# CPU_ETH.net
KiCad netlist of a schematic drawn in Altium Designer
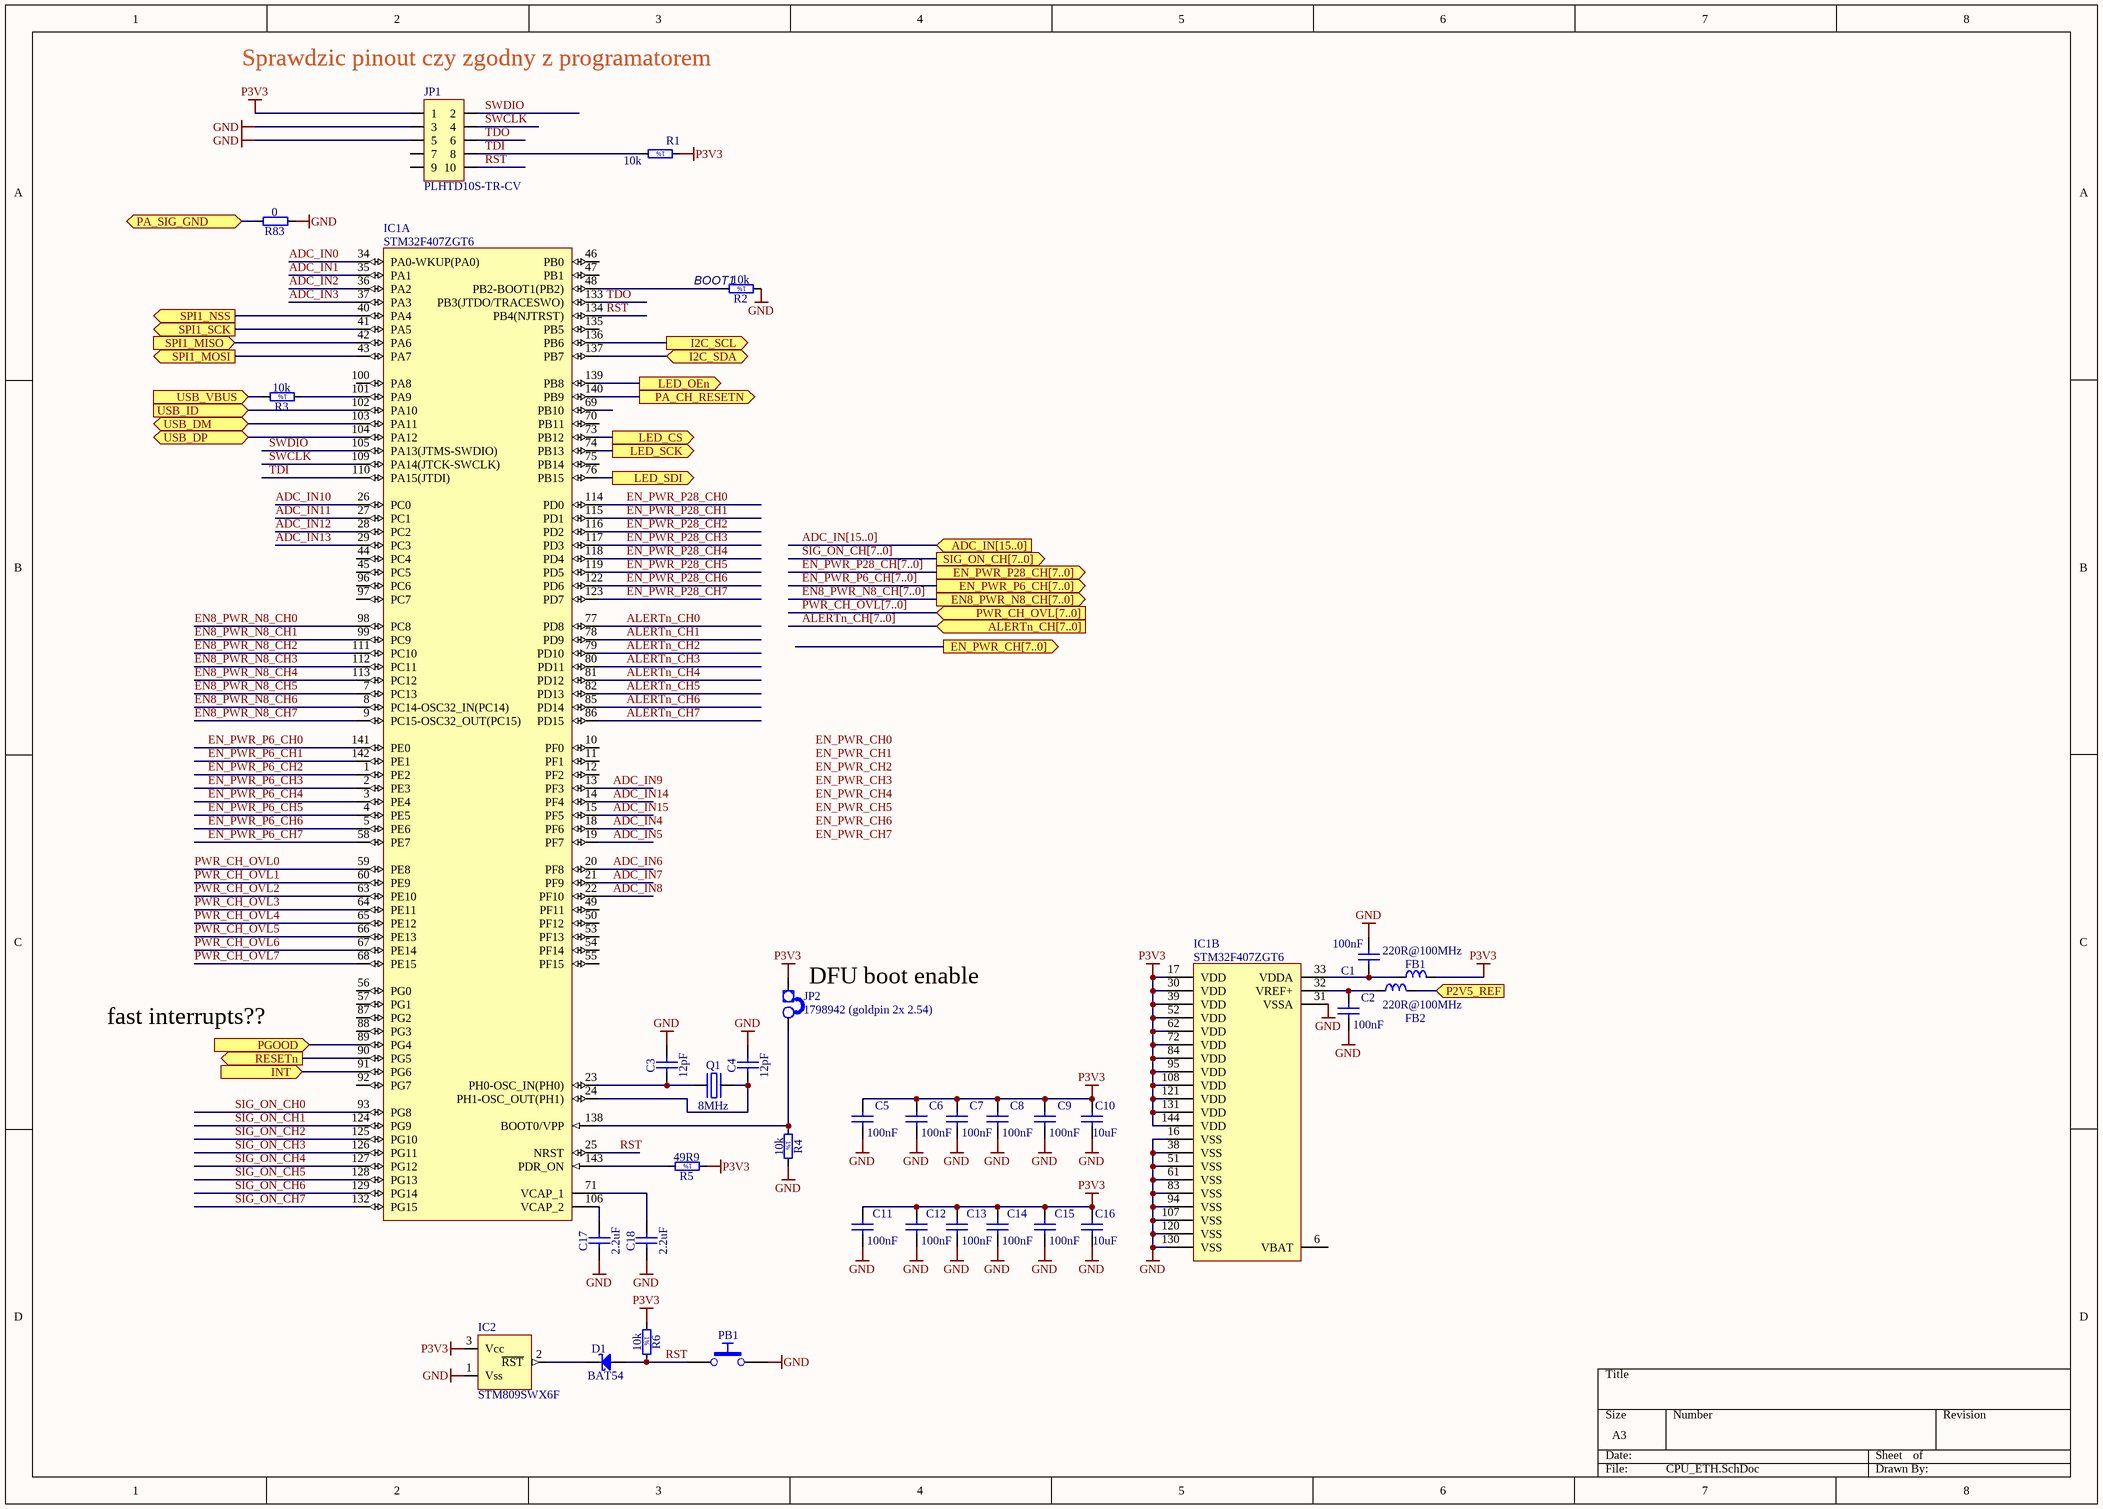
[diagram p0: CPU_ETH.SchDoc]

(export (version "E")
  (design (tool "Eeschema 10.0.6"))
  (components
    (comp (ref "C1")
      (value "100nF")
      (footprint "CAPC0603X33N")
      (description "Non-polarised capacitor")
      (fields
        (field (name "PART NUMBER") "CC0201_100NF_6.3V_10%_X5R")
        (field (name "VOLTAGE") "6.3V")
        (field (name "AUTHOR") "CERN DEM JLC")
      )
      (libsource (lib "Capacitors") (part "Capacitor - non polarized"))
    )
    (comp (ref "C2")
      (value "100nF")
      (footprint "CAPC0603X33N")
      (description "Non-polarised capacitor")
      (fields
        (field (name "PART NUMBER") "CC0201_100NF_6.3V_10%_X5R")
        (field (name "VOLTAGE") "6.3V")
        (field (name "AUTHOR") "CERN DEM JLC")
      )
      (libsource (lib "Capacitors") (part "Capacitor - non polarized"))
    )
    (comp (ref "C3")
      (value "12pF")
      (footprint "CAPC1005X55N")
      (description "Non-polarised capacitor")
      (fields
        (field (name "PART NUMBER") "CC0402_12PF_50V_5%_C0G")
        (field (name "VOLTAGE") "50V")
        (field (name "AUTHOR") "CERN DEM JLC")
      )
      (libsource (lib "Capacitors") (part "Capacitor - non polarized"))
    )
    (comp (ref "C4")
      (value "12pF")
      (footprint "CAPC1005X55N")
      (description "Non-polarised capacitor")
      (fields
        (field (name "PART NUMBER") "CC0402_12PF_50V_5%_C0G")
        (field (name "VOLTAGE") "50V")
        (field (name "AUTHOR") "CERN DEM JLC")
      )
      (libsource (lib "Capacitors") (part "Capacitor - non polarized"))
    )
    (comp (ref "C5")
      (value "100nF")
      (footprint "CAPC0603X33N")
      (description "Non-polarised capacitor")
      (fields
        (field (name "PART NUMBER") "CC0201_100NF_6.3V_10%_X5R")
        (field (name "VOLTAGE") "6.3V")
        (field (name "AUTHOR") "CERN DEM JLC")
      )
      (libsource (lib "Capacitors") (part "Capacitor - non polarized"))
    )
    (comp (ref "C6")
      (value "100nF")
      (footprint "CAPC0603X33N")
      (description "Non-polarised capacitor")
      (fields
        (field (name "PART NUMBER") "CC0201_100NF_6.3V_10%_X5R")
        (field (name "VOLTAGE") "6.3V")
        (field (name "AUTHOR") "CERN DEM JLC")
      )
      (libsource (lib "Capacitors") (part "Capacitor - non polarized"))
    )
    (comp (ref "C7")
      (value "100nF")
      (footprint "CAPC0603X33N")
      (description "Non-polarised capacitor")
      (fields
        (field (name "PART NUMBER") "CC0201_100NF_6.3V_10%_X5R")
        (field (name "VOLTAGE") "6.3V")
        (field (name "AUTHOR") "CERN DEM JLC")
      )
      (libsource (lib "Capacitors") (part "Capacitor - non polarized"))
    )
    (comp (ref "C8")
      (value "100nF")
      (footprint "CAPC0603X33N")
      (description "Non-polarised capacitor")
      (fields
        (field (name "PART NUMBER") "CC0201_100NF_6.3V_10%_X5R")
        (field (name "VOLTAGE") "6.3V")
        (field (name "AUTHOR") "CERN DEM JLC")
      )
      (libsource (lib "Capacitors") (part "Capacitor - non polarized"))
    )
    (comp (ref "C9")
      (value "100nF")
      (footprint "CAPC0603X33N")
      (description "Non-polarised capacitor")
      (fields
        (field (name "PART NUMBER") "CC0201_100NF_6.3V_10%_X5R")
        (field (name "VOLTAGE") "6.3V")
        (field (name "AUTHOR") "CERN DEM JLC")
      )
      (libsource (lib "Capacitors") (part "Capacitor - non polarized"))
    )
    (comp (ref "C10")
      (value "10uF")
      (footprint "CAPC2012X135N")
      (description "Non-polarised capacitor")
      (fields
        (field (name "PART NUMBER") "CC0805_10UF_10V_10%_X7R")
        (field (name "VOLTAGE") "10V")
        (field (name "AUTHOR") "CERN DEM JLC")
      )
      (libsource (lib "Capacitors") (part "Capacitor - non polarized"))
    )
    (comp (ref "C11")
      (value "100nF")
      (footprint "CAPC0603X33N")
      (description "Non-polarised capacitor")
      (fields
        (field (name "PART NUMBER") "CC0201_100NF_6.3V_10%_X5R")
        (field (name "VOLTAGE") "6.3V")
        (field (name "AUTHOR") "CERN DEM JLC")
      )
      (libsource (lib "Capacitors") (part "Capacitor - non polarized"))
    )
    (comp (ref "C12")
      (value "100nF")
      (footprint "CAPC0603X33N")
      (description "Non-polarised capacitor")
      (fields
        (field (name "PART NUMBER") "CC0201_100NF_6.3V_10%_X5R")
        (field (name "VOLTAGE") "6.3V")
        (field (name "AUTHOR") "CERN DEM JLC")
      )
      (libsource (lib "Capacitors") (part "Capacitor - non polarized"))
    )
    (comp (ref "C13")
      (value "100nF")
      (footprint "CAPC0603X33N")
      (description "Non-polarised capacitor")
      (fields
        (field (name "PART NUMBER") "CC0201_100NF_6.3V_10%_X5R")
        (field (name "VOLTAGE") "6.3V")
        (field (name "AUTHOR") "CERN DEM JLC")
      )
      (libsource (lib "Capacitors") (part "Capacitor - non polarized"))
    )
    (comp (ref "C14")
      (value "100nF")
      (footprint "CAPC0603X33N")
      (description "Non-polarised capacitor")
      (fields
        (field (name "PART NUMBER") "CC0201_100NF_6.3V_10%_X5R")
        (field (name "VOLTAGE") "6.3V")
        (field (name "AUTHOR") "CERN DEM JLC")
      )
      (libsource (lib "Capacitors") (part "Capacitor - non polarized"))
    )
    (comp (ref "C15")
      (value "100nF")
      (footprint "CAPC0603X33N")
      (description "Non-polarised capacitor")
      (fields
        (field (name "PART NUMBER") "CC0201_100NF_6.3V_10%_X5R")
        (field (name "VOLTAGE") "6.3V")
        (field (name "AUTHOR") "CERN DEM JLC")
      )
      (libsource (lib "Capacitors") (part "Capacitor - non polarized"))
    )
    (comp (ref "C16")
      (value "10uF")
      (footprint "CAPC2012X135N")
      (description "Non-polarised capacitor")
      (fields
        (field (name "PART NUMBER") "CC0805_10UF_10V_10%_X7R")
        (field (name "VOLTAGE") "10V")
        (field (name "AUTHOR") "CERN DEM JLC")
      )
      (libsource (lib "Capacitors") (part "Capacitor - non polarized"))
    )
    (comp (ref "C17")
      (value "2.2uF")
      (footprint "CAPC1608X90N")
      (description "Non-polarised capacitor")
      (fields
        (field (name "PART NUMBER") "CC0603_2.2UF_10V_20%_X7R")
        (field (name "VOLTAGE") "10V")
        (field (name "AUTHOR") "CERN DEM JLC")
      )
      (libsource (lib "Capacitors") (part "Capacitor - non polarized"))
    )
    (comp (ref "C18")
      (value "2.2uF")
      (footprint "CAPC1608X90N")
      (description "Non-polarised capacitor")
      (fields
        (field (name "PART NUMBER") "CC0603_2.2UF_10V_20%_X7R")
        (field (name "VOLTAGE") "10V")
        (field (name "AUTHOR") "CERN DEM JLC")
      )
      (libsource (lib "Capacitors") (part "Capacitor - non polarized"))
    )
    (comp (ref "D1")
      (value "BAT54")
      (footprint "SOT95P240X130-3N")
      (description "Diode Schottky  Anode Pin 1 Cathode Pin 3 (Pas de pin 2)")
      (fields
        (field (name "VOLTAGE") "30V")
        (field (name "POWER") "200mA")
        (field (name "AUTHOR") "CERN DEM JLC")
      )
      (libsource (lib "ICs And Semiconductors") (part "Diode Schottky A1C3"))
    )
    (comp (ref "FB1")
      (value "220R@100MHz")
      (footprint "INDC2012X105N")
      (description "Inductor")
      (fields
        (field (name "PART NUMBER") "IND0805_MURATA_BLM21PG221SN1D")
        (field (name "POWER") "2A")
        (field (name "AUTHOR") "CERN DEM JLC")
      )
      (libsource (lib "Inductors & Transformers") (part "Inductor"))
    )
    (comp (ref "FB2")
      (value "220R@100MHz")
      (footprint "INDC2012X105N")
      (description "Inductor")
      (fields
        (field (name "PART NUMBER") "IND0805_MURATA_BLM21PG221SN1D")
        (field (name "POWER") "2A")
        (field (name "AUTHOR") "CERN DEM JLC")
      )
      (libsource (lib "Inductors & Transformers") (part "Inductor"))
    )
    (comp (ref "IC1")
      (value "STM32F407ZGT6")
      (footprint "QFP50P2200X2200X160-144N")
      (fields (field (name "MANUFACTURER") "ST MICROELECTRONICS") (field (name "AUTHOR") "CERN DEM MR"))
      (libsource (lib "ICs And Semiconductors") (part "STM32F407ZGT6"))
    )
    (comp (ref "IC2")
      (value "STM809SWX6F")
      (footprint "SOT-23")
      (description "2.93V  Reset circuit")
      (libsource (lib "LIBRARY_SCH") (part "VMON_STM809"))
    )
    (comp (ref "JP1")
      (value "PLHTD10S-TR-CV")
      (footprint "PLHTD10S-TR-CV")
      (description "1.27 mm dual row goldpin (Maritex)")
      (libsource (lib "LIBRARY_SCH") (part "CON_2x5 1.27 SMT Male"))
    )
    (comp (ref "JP2")
      (value "1798942 (goldpin 2x 2.54)")
      (footprint "jump")
      (description "Jumper")
      (libsource (lib "LIBRARY_SCH") (part "JUMPER"))
    )
    (comp (ref "PB1")
      (value "Push Button")
      (footprint "PB_TYCO_FSMSM")
      (description "Push-Button Switch SPDT")
      (fields
        (field (name "PART NUMBER") "PB_TYCO_FSMSM")
        (field (name "MANUFACTURER") "TYCO ELECTRONICS")
        (field (name "AUTHOR") "CERN DEM JLC")
      )
      (libsource (lib "Eletro-mechanical") (part "PB SPST 1NO-2NO"))
    )
    (comp (ref "Q1")
      (value "8MHz")
      (footprint "XTAL_TXC_7A")
      (description "Quartz Crystal")
      (fields
        (field (name "PART NUMBER") "XTAL_8MHZ_TXC_7A-8.000MAAE-T")
        (field (name "MANUFACTURER") "TXC CORPORATION")
        (field (name "AUTHOR") "CERN DEM JLC")
      )
      (libsource (lib "ICs And Semiconductors") (part "Quartz Crystal"))
    )
    (comp (ref "R1")
      (value "10k")
      (footprint "RESC1005X40N")
      (description "Resistor - 1%")
      (fields
        (field (name "PART NUMBER") "R0402_10K_1%_0.0625W_100PPM")
        (field (name "POWER") "0.0625W")
        (field (name "AUTHOR") "CERN DEM JLC")
      )
      (libsource (lib "Resistors") (part "Resistor - 1%"))
    )
    (comp (ref "R2")
      (value "10k")
      (footprint "RESC1005X40N")
      (description "Resistor - 1%")
      (fields
        (field (name "PART NUMBER") "R0402_10K_1%_0.0625W_100PPM")
        (field (name "POWER") "0.0625W")
        (field (name "AUTHOR") "CERN DEM JLC")
      )
      (libsource (lib "Resistors") (part "Resistor - 1%"))
    )
    (comp (ref "R3")
      (value "10k")
      (footprint "RESC1005X40N")
      (description "Resistor - 1%")
      (fields
        (field (name "PART NUMBER") "R0402_10K_1%_0.0625W_100PPM")
        (field (name "POWER") "0.0625W")
        (field (name "AUTHOR") "CERN DEM JLC")
      )
      (libsource (lib "Resistors") (part "Resistor - 1%"))
    )
    (comp (ref "R4")
      (value "10k")
      (footprint "RESC1005X40N")
      (description "Resistor - 1%")
      (fields
        (field (name "PART NUMBER") "R0402_10K_1%_0.0625W_100PPM")
        (field (name "POWER") "0.0625W")
        (field (name "AUTHOR") "CERN DEM JLC")
      )
      (libsource (lib "Resistors") (part "Resistor - 1%"))
    )
    (comp (ref "R5")
      (value "49R9")
      (footprint "RESC1005X40N")
      (description "Resistor - 1%")
      (fields
        (field (name "PART NUMBER") "R0402_49R9_1%_0.0625W_100PPM")
        (field (name "POWER") "0.0625W")
        (field (name "AUTHOR") "CERN DEM JLC")
      )
      (libsource (lib "Resistors") (part "Resistor - 1%"))
    )
    (comp (ref "R6")
      (value "10k")
      (footprint "RESC1005X40N")
      (description "Resistor - 1%")
      (fields
        (field (name "PART NUMBER") "R0402_10K_1%_0.0625W_100PPM")
        (field (name "POWER") "0.0625W")
        (field (name "AUTHOR") "CERN DEM JLC")
      )
      (libsource (lib "Resistors") (part "Resistor - 1%"))
    )
    (comp (ref "R83")
      (value "0")
      (footprint "RESC1005X40N")
      (description "Resistor")
      (fields
        (field (name "PART NUMBER") "R0402_0R_JUMPER")
        (field (name "MANUFACTURER") "GENERIC")
        (field (name "AUTHOR") "CERN DEM JLC")
      )
      (libsource (lib "Resistors") (part "Resistor"))
    )
  )
  (nets
    (net (code "1") (name "/ADC_IN0") (class "Default")
      (node (ref "IC1") (pin "34") (pinfunction "PA0-WKUP(PA0)_34") (pintype "bidirectional"))
    )
    (net (code "2") (name "/ADC_IN1") (class "Default")
      (node (ref "IC1") (pin "35") (pinfunction "PA1_35") (pintype "bidirectional"))
    )
    (net (code "3") (name "/ADC_IN2") (class "Default")
      (node (ref "IC1") (pin "36") (pinfunction "PA2_36") (pintype "bidirectional"))
    )
    (net (code "4") (name "/ADC_IN3") (class "Default")
      (node (ref "IC1") (pin "37") (pinfunction "PA3_37") (pintype "bidirectional"))
    )
    (net (code "5") (name "/ADC_IN4") (class "Default")
      (node (ref "IC1") (pin "18") (pinfunction "PF6_18") (pintype "bidirectional"))
    )
    (net (code "6") (name "/ADC_IN5") (class "Default")
      (node (ref "IC1") (pin "19") (pinfunction "PF7_19") (pintype "bidirectional"))
    )
    (net (code "7") (name "/ADC_IN6") (class "Default")
      (node (ref "IC1") (pin "20") (pinfunction "PF8_20") (pintype "bidirectional"))
    )
    (net (code "8") (name "/ADC_IN7") (class "Default")
      (node (ref "IC1") (pin "21") (pinfunction "PF9_21") (pintype "bidirectional"))
    )
    (net (code "9") (name "/ADC_IN8") (class "Default")
      (node (ref "IC1") (pin "22") (pinfunction "PF10_22") (pintype "bidirectional"))
    )
    (net (code "10") (name "/ADC_IN9") (class "Default")
      (node (ref "IC1") (pin "13") (pinfunction "PF3_13") (pintype "bidirectional"))
    )
    (net (code "11") (name "/ADC_IN10") (class "Default")
      (node (ref "IC1") (pin "26") (pinfunction "PC0_26") (pintype "bidirectional"))
    )
    (net (code "12") (name "/ADC_IN11") (class "Default")
      (node (ref "IC1") (pin "27") (pinfunction "PC1_27") (pintype "bidirectional"))
    )
    (net (code "13") (name "/ADC_IN12") (class "Default")
      (node (ref "IC1") (pin "28") (pinfunction "PC2_28") (pintype "bidirectional"))
    )
    (net (code "14") (name "/ADC_IN13") (class "Default")
      (node (ref "IC1") (pin "29") (pinfunction "PC3_29") (pintype "bidirectional"))
    )
    (net (code "15") (name "/ADC_IN14") (class "Default")
      (node (ref "IC1") (pin "14") (pinfunction "PF4_14") (pintype "bidirectional"))
    )
    (net (code "16") (name "/ADC_IN15") (class "Default")
      (node (ref "IC1") (pin "15") (pinfunction "PF5_15") (pintype "bidirectional"))
    )
    (net (code "18") (name "/ALERTn_CH0") (class "Default")
      (node (ref "IC1") (pin "77") (pinfunction "PD8_77") (pintype "bidirectional"))
    )
    (net (code "19") (name "/ALERTn_CH1") (class "Default")
      (node (ref "IC1") (pin "78") (pinfunction "PD9_78") (pintype "bidirectional"))
    )
    (net (code "20") (name "/ALERTn_CH2") (class "Default")
      (node (ref "IC1") (pin "79") (pinfunction "PD10_79") (pintype "bidirectional"))
    )
    (net (code "21") (name "/ALERTn_CH3") (class "Default")
      (node (ref "IC1") (pin "80") (pinfunction "PD11_80") (pintype "bidirectional"))
    )
    (net (code "22") (name "/ALERTn_CH4") (class "Default")
      (node (ref "IC1") (pin "81") (pinfunction "PD12_81") (pintype "bidirectional"))
    )
    (net (code "23") (name "/ALERTn_CH5") (class "Default")
      (node (ref "IC1") (pin "82") (pinfunction "PD13_82") (pintype "bidirectional"))
    )
    (net (code "24") (name "/ALERTn_CH6") (class "Default")
      (node (ref "IC1") (pin "85") (pinfunction "PD14_85") (pintype "bidirectional"))
    )
    (net (code "25") (name "/ALERTn_CH7") (class "Default")
      (node (ref "IC1") (pin "86") (pinfunction "PD15_86") (pintype "bidirectional"))
    )
    (net (code "27") (name "/EN8_PWR_N8_CH0") (class "Default")
      (node (ref "IC1") (pin "98") (pinfunction "PC8_98") (pintype "bidirectional"))
    )
    (net (code "28") (name "/EN8_PWR_N8_CH1") (class "Default")
      (node (ref "IC1") (pin "99") (pinfunction "PC9_99") (pintype "bidirectional"))
    )
    (net (code "29") (name "/EN8_PWR_N8_CH2") (class "Default")
      (node (ref "IC1") (pin "111") (pinfunction "PC10_111") (pintype "bidirectional"))
    )
    (net (code "30") (name "/EN8_PWR_N8_CH3") (class "Default")
      (node (ref "IC1") (pin "112") (pinfunction "PC11_112") (pintype "bidirectional"))
    )
    (net (code "31") (name "/EN8_PWR_N8_CH4") (class "Default")
      (node (ref "IC1") (pin "113") (pinfunction "PC12_113") (pintype "bidirectional"))
    )
    (net (code "32") (name "/EN8_PWR_N8_CH5") (class "Default")
      (node (ref "IC1") (pin "7") (pinfunction "PC13_7") (pintype "bidirectional"))
    )
    (net (code "33") (name "/EN8_PWR_N8_CH6") (class "Default")
      (node (ref "IC1") (pin "8") (pinfunction "PC14-OSC32_IN(PC14)_8") (pintype "bidirectional"))
    )
    (net (code "34") (name "/EN8_PWR_N8_CH7") (class "Default")
      (node (ref "IC1") (pin "9") (pinfunction "PC15-OSC32_OUT(PC15)_9") (pintype "bidirectional"))
    )
    (net (code "45") (name "/EN_PWR_P6_CH0") (class "Default")
      (node (ref "IC1") (pin "141") (pinfunction "PE0_141") (pintype "bidirectional"))
    )
    (net (code "46") (name "/EN_PWR_P6_CH1") (class "Default")
      (node (ref "IC1") (pin "142") (pinfunction "PE1_142") (pintype "bidirectional"))
    )
    (net (code "47") (name "/EN_PWR_P6_CH2") (class "Default")
      (node (ref "IC1") (pin "1") (pinfunction "PE2_1") (pintype "bidirectional"))
    )
    (net (code "48") (name "/EN_PWR_P6_CH3") (class "Default")
      (node (ref "IC1") (pin "2") (pinfunction "PE3_2") (pintype "bidirectional"))
    )
    (net (code "49") (name "/EN_PWR_P6_CH4") (class "Default")
      (node (ref "IC1") (pin "3") (pinfunction "PE4_3") (pintype "bidirectional"))
    )
    (net (code "50") (name "/EN_PWR_P6_CH5") (class "Default")
      (node (ref "IC1") (pin "4") (pinfunction "PE5_4") (pintype "bidirectional"))
    )
    (net (code "51") (name "/EN_PWR_P6_CH6") (class "Default")
      (node (ref "IC1") (pin "5") (pinfunction "PE6_5") (pintype "bidirectional"))
    )
    (net (code "52") (name "/EN_PWR_P6_CH7") (class "Default")
      (node (ref "IC1") (pin "58") (pinfunction "PE7_58") (pintype "bidirectional"))
    )
    (net (code "54") (name "/EN_PWR_P28_CH0") (class "Default")
      (node (ref "IC1") (pin "114") (pinfunction "PD0_114") (pintype "bidirectional"))
    )
    (net (code "55") (name "/EN_PWR_P28_CH1") (class "Default")
      (node (ref "IC1") (pin "115") (pinfunction "PD1_115") (pintype "bidirectional"))
    )
    (net (code "56") (name "/EN_PWR_P28_CH2") (class "Default")
      (node (ref "IC1") (pin "116") (pinfunction "PD2_116") (pintype "bidirectional"))
    )
    (net (code "57") (name "/EN_PWR_P28_CH3") (class "Default")
      (node (ref "IC1") (pin "117") (pinfunction "PD3_117") (pintype "bidirectional"))
    )
    (net (code "58") (name "/EN_PWR_P28_CH4") (class "Default")
      (node (ref "IC1") (pin "118") (pinfunction "PD4_118") (pintype "bidirectional"))
    )
    (net (code "59") (name "/EN_PWR_P28_CH5") (class "Default")
      (node (ref "IC1") (pin "119") (pinfunction "PD5_119") (pintype "bidirectional"))
    )
    (net (code "60") (name "/EN_PWR_P28_CH6") (class "Default")
      (node (ref "IC1") (pin "122") (pinfunction "PD6_122") (pintype "bidirectional"))
    )
    (net (code "61") (name "/EN_PWR_P28_CH7") (class "Default")
      (node (ref "IC1") (pin "123") (pinfunction "PD7_123") (pintype "bidirectional"))
    )
    (net (code "63") (name "/I2C_SCL") (class "Default")
      (node (ref "IC1") (pin "136") (pinfunction "PB6_136") (pintype "bidirectional"))
    )
    (net (code "64") (name "/I2C_SDA") (class "Default")
      (node (ref "IC1") (pin "137") (pinfunction "PB7_137") (pintype "bidirectional"))
    )
    (net (code "65") (name "/INT") (class "Default")
      (node (ref "IC1") (pin "91") (pinfunction "PG6_91") (pintype "bidirectional"))
    )
    (net (code "66") (name "/LED_CS") (class "Default")
      (node (ref "IC1") (pin "73") (pinfunction "PB12_73") (pintype "bidirectional"))
    )
    (net (code "67") (name "/LED_OEn") (class "Default")
      (node (ref "IC1") (pin "139") (pinfunction "PB8_139") (pintype "bidirectional"))
    )
    (net (code "68") (name "/LED_SCK") (class "Default")
      (node (ref "IC1") (pin "74") (pinfunction "PB13_74") (pintype "bidirectional"))
    )
    (net (code "69") (name "/LED_SDI") (class "Default")
      (node (ref "IC1") (pin "76") (pinfunction "PB15_76") (pintype "bidirectional"))
    )
    (net (code "70") (name "/P2V5_REF") (class "Default")
      (node (ref "FB2") (pin "2") (pinfunction "2_2") (pintype "passive"))
    )
    (net (code "71") (name "/PA_CH_RESETN") (class "Default")
      (node (ref "IC1") (pin "140") (pinfunction "PB9_140") (pintype "bidirectional"))
    )
    (net (code "72") (name "/PA_SIG_GND") (class "Default")
      (node (ref "R83") (pin "2") (pinfunction "2_2") (pintype "passive"))
    )
    (net (code "73") (name "/PGOOD") (class "Default")
      (node (ref "IC1") (pin "89") (pinfunction "PG4_89") (pintype "bidirectional"))
    )
    (net (code "74") (name "/PWR_CH_OVL0") (class "Default")
      (node (ref "IC1") (pin "59") (pinfunction "PE8_59") (pintype "bidirectional"))
    )
    (net (code "75") (name "/PWR_CH_OVL1") (class "Default")
      (node (ref "IC1") (pin "60") (pinfunction "PE9_60") (pintype "bidirectional"))
    )
    (net (code "76") (name "/PWR_CH_OVL2") (class "Default")
      (node (ref "IC1") (pin "63") (pinfunction "PE10_63") (pintype "bidirectional"))
    )
    (net (code "77") (name "/PWR_CH_OVL3") (class "Default")
      (node (ref "IC1") (pin "64") (pinfunction "PE11_64") (pintype "bidirectional"))
    )
    (net (code "78") (name "/PWR_CH_OVL4") (class "Default")
      (node (ref "IC1") (pin "65") (pinfunction "PE12_65") (pintype "bidirectional"))
    )
    (net (code "79") (name "/PWR_CH_OVL5") (class "Default")
      (node (ref "IC1") (pin "66") (pinfunction "PE13_66") (pintype "bidirectional"))
    )
    (net (code "80") (name "/PWR_CH_OVL6") (class "Default")
      (node (ref "IC1") (pin "67") (pinfunction "PE14_67") (pintype "bidirectional"))
    )
    (net (code "81") (name "/PWR_CH_OVL7") (class "Default")
      (node (ref "IC1") (pin "68") (pinfunction "PE15_68") (pintype "bidirectional"))
    )
    (net (code "83") (name "/RESETn") (class "Default")
      (node (ref "IC1") (pin "90") (pinfunction "PG5_90") (pintype "bidirectional"))
    )
    (net (code "84") (name "/RST") (class "Default")
      (node (ref "D1") (pin "1") (pinfunction "A_1") (pintype "passive"))
      (node (ref "IC1") (pin "134") (pinfunction "PB4(NJTRST)_134") (pintype "bidirectional"))
      (node (ref "IC1") (pin "25") (pinfunction "NRST_25") (pintype "bidirectional"))
      (node (ref "JP1") (pin "10") (pinfunction "10_10") (pintype "passive"))
      (node (ref "PB1") (pin "1") (pinfunction "1_1") (pintype "passive"))
      (node (ref "R6") (pin "2") (pinfunction "2_2") (pintype "passive"))
    )
    (net (code "85") (name "/SIG_ON_CH0") (class "Default")
      (node (ref "IC1") (pin "93") (pinfunction "PG8_93") (pintype "bidirectional"))
    )
    (net (code "86") (name "/SIG_ON_CH1") (class "Default")
      (node (ref "IC1") (pin "124") (pinfunction "PG9_124") (pintype "bidirectional"))
    )
    (net (code "87") (name "/SIG_ON_CH2") (class "Default")
      (node (ref "IC1") (pin "125") (pinfunction "PG10_125") (pintype "bidirectional"))
    )
    (net (code "88") (name "/SIG_ON_CH3") (class "Default")
      (node (ref "IC1") (pin "126") (pinfunction "PG11_126") (pintype "bidirectional"))
    )
    (net (code "89") (name "/SIG_ON_CH4") (class "Default")
      (node (ref "IC1") (pin "127") (pinfunction "PG12_127") (pintype "bidirectional"))
    )
    (net (code "90") (name "/SIG_ON_CH5") (class "Default")
      (node (ref "IC1") (pin "128") (pinfunction "PG13_128") (pintype "bidirectional"))
    )
    (net (code "91") (name "/SIG_ON_CH6") (class "Default")
      (node (ref "IC1") (pin "129") (pinfunction "PG14_129") (pintype "bidirectional"))
    )
    (net (code "92") (name "/SIG_ON_CH7") (class "Default")
      (node (ref "IC1") (pin "132") (pinfunction "PG15_132") (pintype "bidirectional"))
    )
    (net (code "94") (name "/SPI1_MISO") (class "Default")
      (node (ref "IC1") (pin "42") (pinfunction "PA6_42") (pintype "bidirectional"))
    )
    (net (code "95") (name "/SPI1_MOSI") (class "Default")
      (node (ref "IC1") (pin "43") (pinfunction "PA7_43") (pintype "bidirectional"))
    )
    (net (code "96") (name "/SPI1_NSS") (class "Default")
      (node (ref "IC1") (pin "40") (pinfunction "PA4_40") (pintype "bidirectional"))
    )
    (net (code "97") (name "/SPI1_SCK") (class "Default")
      (node (ref "IC1") (pin "41") (pinfunction "PA5_41") (pintype "bidirectional"))
    )
    (net (code "98") (name "/SWCLK") (class "Default")
      (node (ref "IC1") (pin "109") (pinfunction "PA14(JTCK-SWCLK)_109") (pintype "bidirectional"))
      (node (ref "JP1") (pin "4") (pinfunction "4_4") (pintype "passive"))
    )
    (net (code "99") (name "/SWDIO") (class "Default")
      (node (ref "IC1") (pin "105") (pinfunction "PA13(JTMS-SWDIO)_105") (pintype "bidirectional"))
      (node (ref "JP1") (pin "2") (pinfunction "2_2") (pintype "passive"))
    )
    (net (code "100") (name "/TDI") (class "Default")
      (node (ref "IC1") (pin "110") (pinfunction "PA15(JTDI)_110") (pintype "bidirectional"))
      (node (ref "JP1") (pin "8") (pinfunction "8_8") (pintype "passive"))
      (node (ref "R1") (pin "2") (pinfunction "2_2") (pintype "passive"))
    )
    (net (code "101") (name "/TDO") (class "Default")
      (node (ref "IC1") (pin "133") (pinfunction "PB3(JTDO/TRACESWO)_133") (pintype "bidirectional"))
      (node (ref "JP1") (pin "6") (pinfunction "6_6") (pintype "passive"))
    )
    (net (code "102") (name "/USB_DM") (class "Default")
      (node (ref "IC1") (pin "103") (pinfunction "PA11_103") (pintype "bidirectional"))
    )
    (net (code "103") (name "/USB_DP") (class "Default")
      (node (ref "IC1") (pin "104") (pinfunction "PA12_104") (pintype "bidirectional"))
    )
    (net (code "104") (name "/USB_ID") (class "Default")
      (node (ref "IC1") (pin "102") (pinfunction "PA10_102") (pintype "bidirectional"))
    )
    (net (code "105") (name "/USB_VBUS") (class "Default")
      (node (ref "R3") (pin "2") (pinfunction "2_2") (pintype "passive"))
    )
    (net (code "106") (name "GND") (class "Default")
      (node (ref "C1") (pin "2") (pinfunction "2_2") (pintype "passive"))
      (node (ref "C10") (pin "2") (pinfunction "2_2") (pintype "passive"))
      (node (ref "C11") (pin "2") (pinfunction "2_2") (pintype "passive"))
      (node (ref "C12") (pin "2") (pinfunction "2_2") (pintype "passive"))
      (node (ref "C13") (pin "2") (pinfunction "2_2") (pintype "passive"))
      (node (ref "C14") (pin "2") (pinfunction "2_2") (pintype "passive"))
      (node (ref "C15") (pin "2") (pinfunction "2_2") (pintype "passive"))
      (node (ref "C16") (pin "2") (pinfunction "2_2") (pintype "passive"))
      (node (ref "C17") (pin "1") (pinfunction "1_1") (pintype "passive"))
      (node (ref "C18") (pin "1") (pinfunction "1_1") (pintype "passive"))
      (node (ref "C2") (pin "2") (pinfunction "2_2") (pintype "passive"))
      (node (ref "C3") (pin "2") (pinfunction "2_2") (pintype "passive"))
      (node (ref "C4") (pin "2") (pinfunction "2_2") (pintype "passive"))
      (node (ref "C5") (pin "2") (pinfunction "2_2") (pintype "passive"))
      (node (ref "C6") (pin "2") (pinfunction "2_2") (pintype "passive"))
      (node (ref "C7") (pin "2") (pinfunction "2_2") (pintype "passive"))
      (node (ref "C8") (pin "2") (pinfunction "2_2") (pintype "passive"))
      (node (ref "C9") (pin "2") (pinfunction "2_2") (pintype "passive"))
      (node (ref "IC1") (pin "107") (pinfunction "VSS_107") (pintype "power_in"))
      (node (ref "IC1") (pin "120") (pinfunction "VSS_120") (pintype "power_in"))
      (node (ref "IC1") (pin "130") (pinfunction "VSS_130") (pintype "power_in"))
      (node (ref "IC1") (pin "16") (pinfunction "VSS_16") (pintype "power_in"))
      (node (ref "IC1") (pin "31") (pinfunction "VSSA_31") (pintype "power_in"))
      (node (ref "IC1") (pin "38") (pinfunction "VSS_38") (pintype "power_in"))
      (node (ref "IC1") (pin "51") (pinfunction "VSS_51") (pintype "power_in"))
      (node (ref "IC1") (pin "61") (pinfunction "VSS_61") (pintype "power_in"))
      (node (ref "IC1") (pin "83") (pinfunction "VSS_83") (pintype "power_in"))
      (node (ref "IC1") (pin "94") (pinfunction "VSS_94") (pintype "power_in"))
      (node (ref "IC2") (pin "1") (pinfunction "Vss_1") (pintype "power_in"))
      (node (ref "JP1") (pin "3") (pinfunction "3_3") (pintype "passive"))
      (node (ref "JP1") (pin "5") (pinfunction "5_5") (pintype "passive"))
      (node (ref "PB1") (pin "2") (pinfunction "2_2") (pintype "passive"))
      (node (ref "R2") (pin "1") (pinfunction "1_1") (pintype "passive"))
      (node (ref "R4") (pin "2") (pinfunction "2_2") (pintype "passive"))
      (node (ref "R83") (pin "1") (pinfunction "1_1") (pintype "passive"))
    )
    (net (code "107") (name "Net-(D1-C)") (class "Default")
      (node (ref "D1") (pin "3") (pinfunction "C_3") (pintype "passive"))
      (node (ref "IC2") (pin "2") (pinfunction "~{RST}_2") (pintype "output"))
    )
    (net (code "108") (name "Net-(IC1A-BOOT0{slash}VPP)") (class "Default")
      (node (ref "IC1") (pin "138") (pinfunction "BOOT0/VPP_138") (pintype "input"))
      (node (ref "JP2") (pin "2") (pinfunction "E2_2") (pintype "passive"))
      (node (ref "R4") (pin "1") (pinfunction "1_1") (pintype "passive"))
    )
    (net (code "109") (name "Net-(IC1A-PA9)") (class "Default")
      (node (ref "IC1") (pin "101") (pinfunction "PA9_101") (pintype "bidirectional"))
      (node (ref "R3") (pin "1") (pinfunction "1_1") (pintype "passive"))
    )
    (net (code "110") (name "Net-(IC1A-PB2-BOOT1(PB2))") (class "Default")
      (node (ref "IC1") (pin "48") (pinfunction "PB2-BOOT1(PB2)_48") (pintype "bidirectional"))
      (node (ref "R2") (pin "2") (pinfunction "2_2") (pintype "passive"))
    )
    (net (code "111") (name "Net-(IC1A-PDR_ON)") (class "Default")
      (node (ref "IC1") (pin "143") (pinfunction "PDR_ON_143") (pintype "input"))
      (node (ref "R5") (pin "2") (pinfunction "2_2") (pintype "passive"))
    )
    (net (code "112") (name "Net-(IC1A-PH0-OSC_IN(PH0))") (class "Default")
      (node (ref "C3") (pin "1") (pinfunction "1_1") (pintype "passive"))
      (node (ref "IC1") (pin "23") (pinfunction "PH0-OSC_IN(PH0)_23") (pintype "bidirectional"))
      (node (ref "Q1") (pin "1") (pinfunction "OSC1_1") (pintype "passive"))
    )
    (net (code "113") (name "Net-(IC1A-PH1-OSC_OUT(PH1))") (class "Default")
      (node (ref "C4") (pin "1") (pinfunction "1_1") (pintype "passive"))
      (node (ref "IC1") (pin "24") (pinfunction "PH1-OSC_OUT(PH1)_24") (pintype "bidirectional"))
      (node (ref "Q1") (pin "2") (pinfunction "OSC2_2") (pintype "passive"))
    )
    (net (code "114") (name "Net-(IC1A-VCAP_1)") (class "Default")
      (node (ref "C18") (pin "2") (pinfunction "2_2") (pintype "passive"))
      (node (ref "IC1") (pin "71") (pinfunction "VCAP_1_71") (pintype "power_in"))
    )
    (net (code "115") (name "Net-(IC1A-VCAP_2)") (class "Default")
      (node (ref "C17") (pin "2") (pinfunction "2_2") (pintype "passive"))
      (node (ref "IC1") (pin "106") (pinfunction "VCAP_2_106") (pintype "power_in"))
    )
    (net (code "116") (name "Net-(IC1B-VDDA)") (class "Default")
      (node (ref "C1") (pin "1") (pinfunction "1_1") (pintype "passive"))
      (node (ref "FB1") (pin "1") (pinfunction "1_1") (pintype "passive"))
      (node (ref "IC1") (pin "33") (pinfunction "VDDA_33") (pintype "power_in"))
    )
    (net (code "117") (name "Net-(IC1B-VREF+)") (class "Default")
      (node (ref "C2") (pin "1") (pinfunction "1_1") (pintype "passive"))
      (node (ref "FB2") (pin "1") (pinfunction "1_1") (pintype "passive"))
      (node (ref "IC1") (pin "32") (pinfunction "VREF+_32") (pintype "power_in"))
    )
    (net (code "118") (name "P3V3") (class "Default")
      (node (ref "C10") (pin "1") (pinfunction "1_1") (pintype "passive"))
      (node (ref "C11") (pin "1") (pinfunction "1_1") (pintype "passive"))
      (node (ref "C12") (pin "1") (pinfunction "1_1") (pintype "passive"))
      (node (ref "C13") (pin "1") (pinfunction "1_1") (pintype "passive"))
      (node (ref "C14") (pin "1") (pinfunction "1_1") (pintype "passive"))
      (node (ref "C15") (pin "1") (pinfunction "1_1") (pintype "passive"))
      (node (ref "C16") (pin "1") (pinfunction "1_1") (pintype "passive"))
      (node (ref "C5") (pin "1") (pinfunction "1_1") (pintype "passive"))
      (node (ref "C6") (pin "1") (pinfunction "1_1") (pintype "passive"))
      (node (ref "C7") (pin "1") (pinfunction "1_1") (pintype "passive"))
      (node (ref "C8") (pin "1") (pinfunction "1_1") (pintype "passive"))
      (node (ref "C9") (pin "1") (pinfunction "1_1") (pintype "passive"))
      (node (ref "FB1") (pin "2") (pinfunction "2_2") (pintype "passive"))
      (node (ref "IC1") (pin "108") (pinfunction "VDD_108") (pintype "power_in"))
      (node (ref "IC1") (pin "121") (pinfunction "VDD_121") (pintype "power_in"))
      (node (ref "IC1") (pin "131") (pinfunction "VDD_131") (pintype "power_in"))
      (node (ref "IC1") (pin "144") (pinfunction "VDD_144") (pintype "power_in"))
      (node (ref "IC1") (pin "17") (pinfunction "VDD_17") (pintype "power_in"))
      (node (ref "IC1") (pin "30") (pinfunction "VDD_30") (pintype "power_in"))
      (node (ref "IC1") (pin "39") (pinfunction "VDD_39") (pintype "power_in"))
      (node (ref "IC1") (pin "52") (pinfunction "VDD_52") (pintype "power_in"))
      (node (ref "IC1") (pin "62") (pinfunction "VDD_62") (pintype "power_in"))
      (node (ref "IC1") (pin "72") (pinfunction "VDD_72") (pintype "power_in"))
      (node (ref "IC1") (pin "84") (pinfunction "VDD_84") (pintype "power_in"))
      (node (ref "IC1") (pin "95") (pinfunction "VDD_95") (pintype "power_in"))
      (node (ref "IC2") (pin "3") (pinfunction "Vcc_3") (pintype "power_in"))
      (node (ref "JP1") (pin "1") (pinfunction "1_1") (pintype "passive"))
      (node (ref "JP2") (pin "1") (pinfunction "E1_1") (pintype "passive"))
      (node (ref "R1") (pin "1") (pinfunction "1_1") (pintype "passive"))
      (node (ref "R5") (pin "1") (pinfunction "1_1") (pintype "passive"))
      (node (ref "R6") (pin "1") (pinfunction "1_1") (pintype "passive"))
    )
    (net (code "119") (name "unconnected-(IC1A-PA8-Pad100)") (class "Default")
      (node (ref "IC1") (pin "100") (pinfunction "PA8_100") (pintype "bidirectional"))
    )
    (net (code "120") (name "unconnected-(IC1A-PB0-Pad46)") (class "Default")
      (node (ref "IC1") (pin "46") (pinfunction "PB0_46") (pintype "bidirectional"))
    )
    (net (code "121") (name "unconnected-(IC1A-PB1-Pad47)") (class "Default")
      (node (ref "IC1") (pin "47") (pinfunction "PB1_47") (pintype "bidirectional"))
    )
    (net (code "122") (name "unconnected-(IC1A-PB5-Pad135)") (class "Default")
      (node (ref "IC1") (pin "135") (pinfunction "PB5_135") (pintype "bidirectional"))
    )
    (net (code "123") (name "unconnected-(IC1A-PB10-Pad69)") (class "Default")
      (node (ref "IC1") (pin "69") (pinfunction "PB10_69") (pintype "bidirectional"))
    )
    (net (code "124") (name "unconnected-(IC1A-PB11-Pad70)") (class "Default")
      (node (ref "IC1") (pin "70") (pinfunction "PB11_70") (pintype "bidirectional"))
    )
    (net (code "125") (name "unconnected-(IC1A-PB14-Pad75)") (class "Default")
      (node (ref "IC1") (pin "75") (pinfunction "PB14_75") (pintype "bidirectional"))
    )
    (net (code "126") (name "unconnected-(IC1A-PC4-Pad44)") (class "Default")
      (node (ref "IC1") (pin "44") (pinfunction "PC4_44") (pintype "bidirectional"))
    )
    (net (code "127") (name "unconnected-(IC1A-PC5-Pad45)") (class "Default")
      (node (ref "IC1") (pin "45") (pinfunction "PC5_45") (pintype "bidirectional"))
    )
    (net (code "128") (name "unconnected-(IC1A-PC6-Pad96)") (class "Default")
      (node (ref "IC1") (pin "96") (pinfunction "PC6_96") (pintype "bidirectional"))
    )
    (net (code "129") (name "unconnected-(IC1A-PC7-Pad97)") (class "Default")
      (node (ref "IC1") (pin "97") (pinfunction "PC7_97") (pintype "bidirectional"))
    )
    (net (code "130") (name "unconnected-(IC1A-PF0-Pad10)") (class "Default")
      (node (ref "IC1") (pin "10") (pinfunction "PF0_10") (pintype "bidirectional"))
    )
    (net (code "131") (name "unconnected-(IC1A-PF1-Pad11)") (class "Default")
      (node (ref "IC1") (pin "11") (pinfunction "PF1_11") (pintype "bidirectional"))
    )
    (net (code "132") (name "unconnected-(IC1A-PF2-Pad12)") (class "Default")
      (node (ref "IC1") (pin "12") (pinfunction "PF2_12") (pintype "bidirectional"))
    )
    (net (code "133") (name "unconnected-(IC1A-PF11-Pad49)") (class "Default")
      (node (ref "IC1") (pin "49") (pinfunction "PF11_49") (pintype "bidirectional"))
    )
    (net (code "134") (name "unconnected-(IC1A-PF12-Pad50)") (class "Default")
      (node (ref "IC1") (pin "50") (pinfunction "PF12_50") (pintype "bidirectional"))
    )
    (net (code "135") (name "unconnected-(IC1A-PF13-Pad53)") (class "Default")
      (node (ref "IC1") (pin "53") (pinfunction "PF13_53") (pintype "bidirectional"))
    )
    (net (code "136") (name "unconnected-(IC1A-PF14-Pad54)") (class "Default")
      (node (ref "IC1") (pin "54") (pinfunction "PF14_54") (pintype "bidirectional"))
    )
    (net (code "137") (name "unconnected-(IC1A-PF15-Pad55)") (class "Default")
      (node (ref "IC1") (pin "55") (pinfunction "PF15_55") (pintype "bidirectional"))
    )
    (net (code "138") (name "unconnected-(IC1A-PG0-Pad56)") (class "Default")
      (node (ref "IC1") (pin "56") (pinfunction "PG0_56") (pintype "bidirectional"))
    )
    (net (code "139") (name "unconnected-(IC1A-PG1-Pad57)") (class "Default")
      (node (ref "IC1") (pin "57") (pinfunction "PG1_57") (pintype "bidirectional"))
    )
    (net (code "140") (name "unconnected-(IC1A-PG2-Pad87)") (class "Default")
      (node (ref "IC1") (pin "87") (pinfunction "PG2_87") (pintype "bidirectional"))
    )
    (net (code "141") (name "unconnected-(IC1A-PG3-Pad88)") (class "Default")
      (node (ref "IC1") (pin "88") (pinfunction "PG3_88") (pintype "bidirectional"))
    )
    (net (code "142") (name "unconnected-(IC1A-PG7-Pad92)") (class "Default")
      (node (ref "IC1") (pin "92") (pinfunction "PG7_92") (pintype "bidirectional"))
    )
    (net (code "143") (name "unconnected-(IC1B-VBAT-Pad6)") (class "Default")
      (node (ref "IC1") (pin "6") (pinfunction "VBAT_6") (pintype "power_in"))
    )
    (net (code "144") (name "unconnected-(JP1-Pad7)") (class "Default")
      (node (ref "JP1") (pin "7") (pinfunction "7_7") (pintype "passive"))
    )
    (net (code "145") (name "unconnected-(JP1-Pad9)") (class "Default")
      (node (ref "JP1") (pin "9") (pinfunction "9_9") (pintype "passive"))
    )
  )
)
